# PI_Servo_Shield.net
KiCad netlist of a schematic drawn in EAGLE
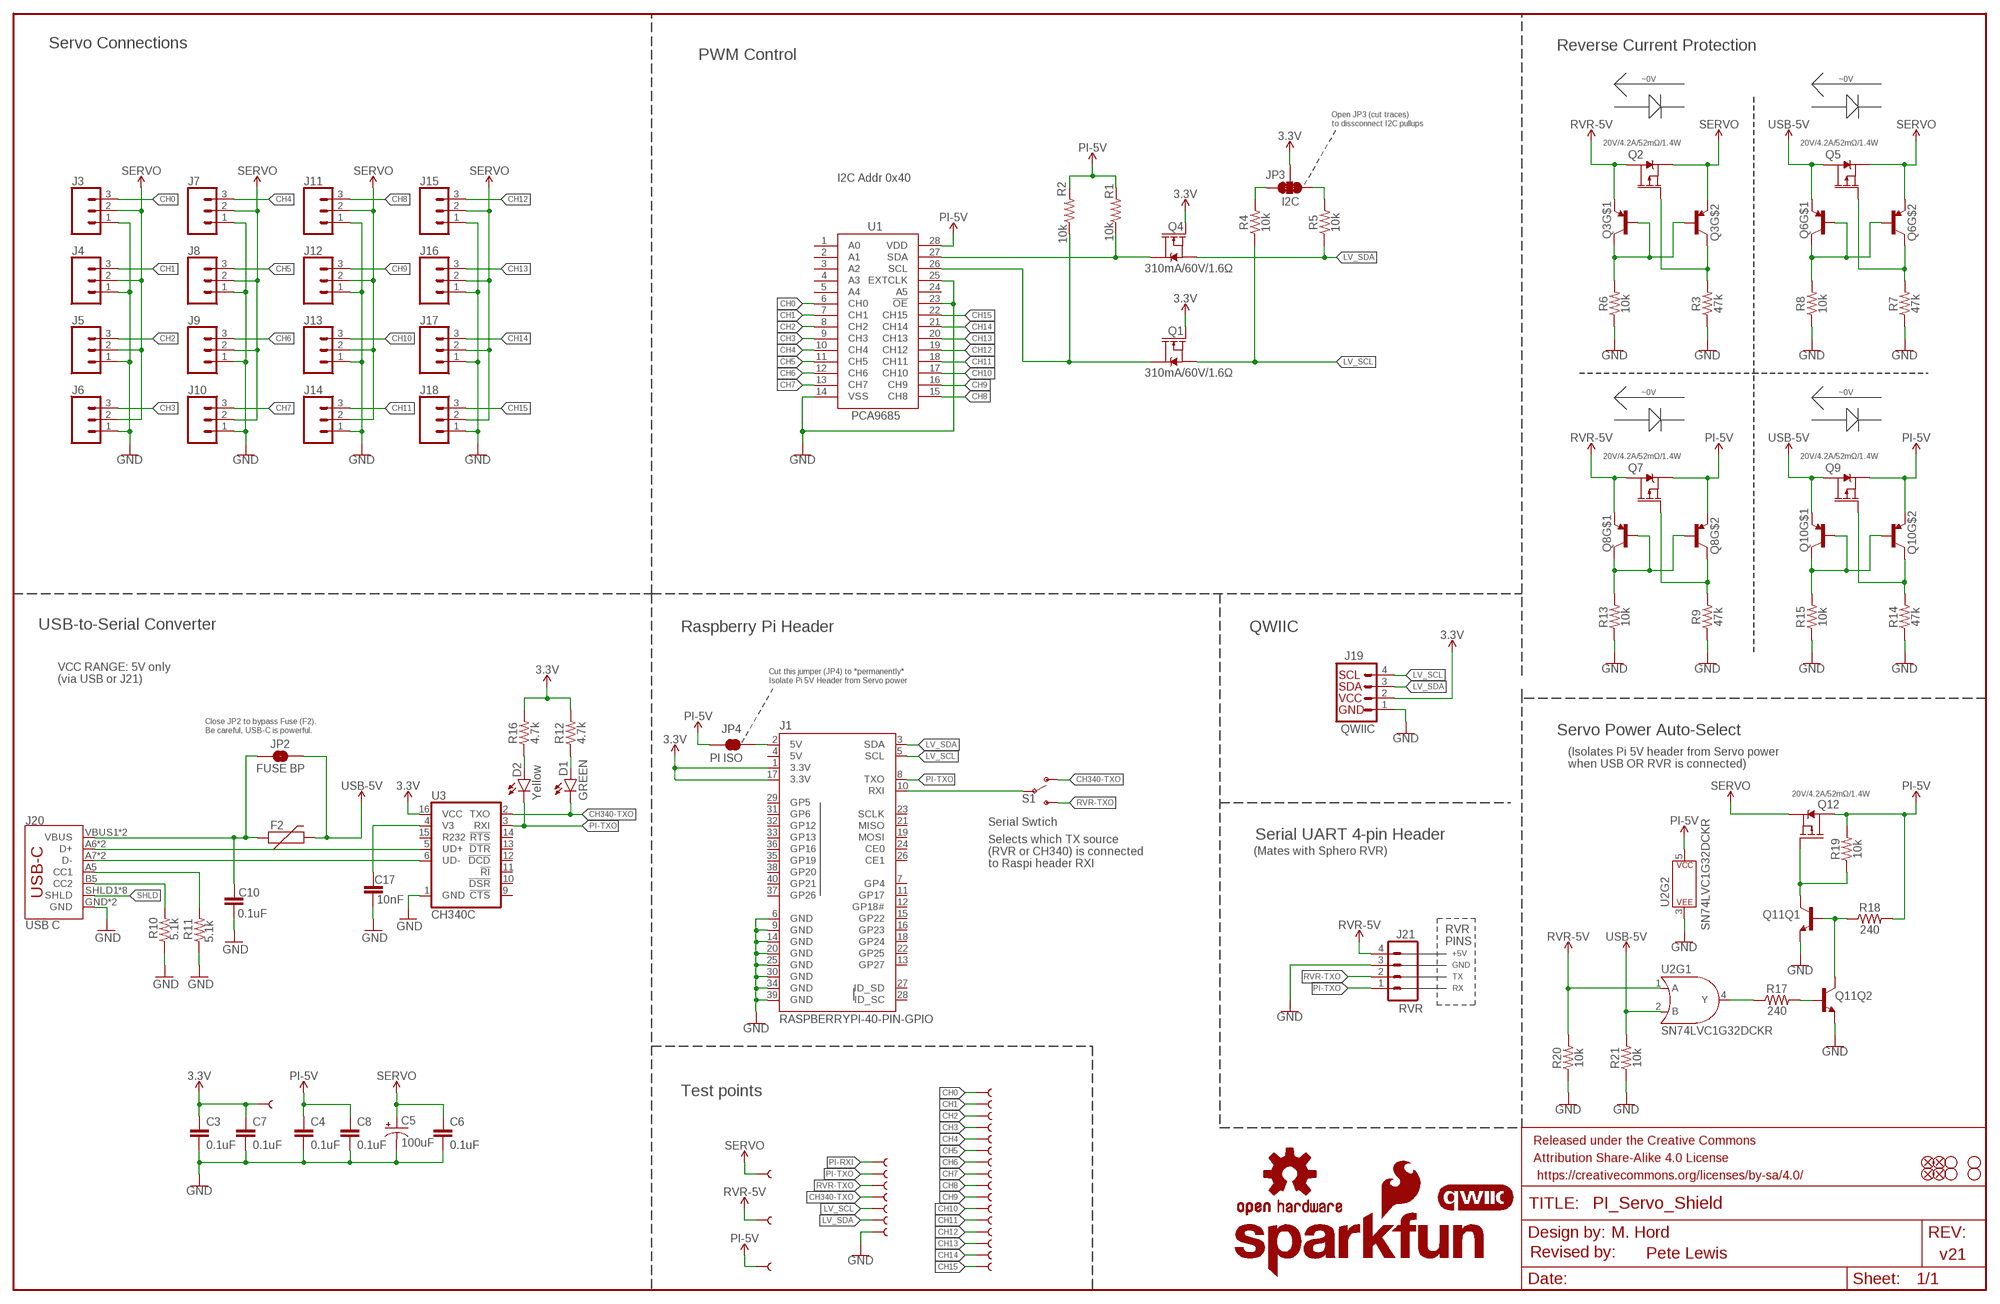
[diagram p0: schematic, sheet 1]

(export (version "E")
  (design (tool "Eeschema 10.0.6"))
  (components
    (comp (ref "C3")
      (value "0.1uF")
      (footprint "eagle-import:0603")
      (libsource (lib "eagle-import") (part "0.1UF-0603-25V-(+80/-20%)"))
    )
    (comp (ref "C4")
      (value "0.1uF")
      (footprint "eagle-import:0603")
      (libsource (lib "eagle-import") (part "0.1UF-0603-25V-(+80/-20%)"))
    )
    (comp (ref "C5")
      (value "100uF")
      (footprint "eagle-import:PANASONIC_D")
      (libsource (lib "eagle-import") (part "100UF-POLAR-25V-20%(ELEC)"))
    )
    (comp (ref "C6")
      (value "0.1uF")
      (footprint "eagle-import:0603")
      (libsource (lib "eagle-import") (part "0.1UF-0603-25V-(+80/-20%)"))
    )
    (comp (ref "C7")
      (value "0.1uF")
      (footprint "eagle-import:0603")
      (libsource (lib "eagle-import") (part "0.1UF-0603-25V-(+80/-20%)"))
    )
    (comp (ref "C8")
      (value "0.1uF")
      (footprint "eagle-import:0603")
      (libsource (lib "eagle-import") (part "0.1UF-0603-25V-(+80/-20%)"))
    )
    (comp (ref "C10")
      (value "0.1uF")
      (footprint "eagle-import:0603")
      (libsource (lib "eagle-import") (part "0.1UF-0603-25V-(+80/-20%)"))
    )
    (comp (ref "C17")
      (value "10nF")
      (footprint "eagle-import:0603")
      (libsource (lib "eagle-import") (part "10NF-0603-50V-10%"))
    )
    (comp (ref "D1")
      (value "GREEN")
      (footprint "eagle-import:LED-0603")
      (libsource (lib "eagle-import") (part "LED-GREEN0603"))
    )
    (comp (ref "D2")
      (value "Yellow")
      (footprint "eagle-import:LED-0603")
      (libsource (lib "eagle-import") (part "LED-YELLOW0603"))
    )
    (comp (ref "F2")
      (value "16V/2.5A(5A TRIP)")
      (footprint "eagle-import:1812")
      (libsource (lib "eagle-import") (part "PPTC_16V_2.5A"))
    )
    (comp (ref "FD1")
      (value "FIDUCIALUFIDUCIAL")
      (footprint "eagle-import:FIDUCIAL-MICRO")
      (libsource (lib "eagle-import") (part "FIDUCIALUFIDUCIAL"))
    )
    (comp (ref "FD2")
      (value "FIDUCIALUFIDUCIAL")
      (footprint "eagle-import:FIDUCIAL-MICRO")
      (libsource (lib "eagle-import") (part "FIDUCIALUFIDUCIAL"))
    )
    (comp (ref "FD3")
      (value "FIDUCIALUFIDUCIAL")
      (footprint "eagle-import:FIDUCIAL-MICRO")
      (libsource (lib "eagle-import") (part "FIDUCIALUFIDUCIAL"))
    )
    (comp (ref "FD4")
      (value "FIDUCIALUFIDUCIAL")
      (footprint "eagle-import:FIDUCIAL-MICRO")
      (libsource (lib "eagle-import") (part "FIDUCIALUFIDUCIAL"))
    )
    (comp (ref "FRAME2")
      (value "FRAME-LEDGER")
      (footprint "eagle-import:CREATIVE_COMMONS")
      (libsource (lib "eagle-import") (part "FRAME-LEDGER"))
    )
    (comp (ref "H1")
      (value "STAND-OFF")
      (footprint "eagle-import:STAND-OFF")
      (libsource (lib "eagle-import") (part "STAND-OFF"))
    )
    (comp (ref "H2")
      (value "STAND-OFF")
      (footprint "eagle-import:STAND-OFF")
      (libsource (lib "eagle-import") (part "STAND-OFF"))
    )
    (comp (ref "H3")
      (value "STAND-OFF")
      (footprint "eagle-import:STAND-OFF")
      (libsource (lib "eagle-import") (part "STAND-OFF"))
    )
    (comp (ref "H4")
      (value "STAND-OFF")
      (footprint "eagle-import:STAND-OFF")
      (libsource (lib "eagle-import") (part "STAND-OFF"))
    )
    (comp (ref "J1")
      (value "RASPBERRYPI-40-PIN-GPIO")
      (footprint "eagle-import:2X20")
      (libsource (lib "eagle-import") (part "RASPBERRYPI-40-PIN-GPIO_PTH_NO_SHROUD"))
    )
    (comp (ref "J3")
      (value "CONN_03")
      (footprint "eagle-import:1X03")
      (libsource (lib "eagle-import") (part "CONN_03"))
    )
    (comp (ref "J4")
      (value "CONN_03")
      (footprint "eagle-import:1X03")
      (libsource (lib "eagle-import") (part "CONN_03"))
    )
    (comp (ref "J5")
      (value "CONN_03")
      (footprint "eagle-import:1X03")
      (libsource (lib "eagle-import") (part "CONN_03"))
    )
    (comp (ref "J6")
      (value "CONN_03")
      (footprint "eagle-import:1X03")
      (libsource (lib "eagle-import") (part "CONN_03"))
    )
    (comp (ref "J7")
      (value "CONN_03")
      (footprint "eagle-import:1X03")
      (libsource (lib "eagle-import") (part "CONN_03"))
    )
    (comp (ref "J8")
      (value "CONN_03")
      (footprint "eagle-import:1X03")
      (libsource (lib "eagle-import") (part "CONN_03"))
    )
    (comp (ref "J9")
      (value "CONN_03")
      (footprint "eagle-import:1X03")
      (libsource (lib "eagle-import") (part "CONN_03"))
    )
    (comp (ref "J10")
      (value "CONN_03")
      (footprint "eagle-import:1X03")
      (libsource (lib "eagle-import") (part "CONN_03"))
    )
    (comp (ref "J11")
      (value "CONN_03")
      (footprint "eagle-import:1X03")
      (libsource (lib "eagle-import") (part "CONN_03"))
    )
    (comp (ref "J12")
      (value "CONN_03")
      (footprint "eagle-import:1X03")
      (libsource (lib "eagle-import") (part "CONN_03"))
    )
    (comp (ref "J13")
      (value "CONN_03")
      (footprint "eagle-import:1X03")
      (libsource (lib "eagle-import") (part "CONN_03"))
    )
    (comp (ref "J14")
      (value "CONN_03")
      (footprint "eagle-import:1X03")
      (libsource (lib "eagle-import") (part "CONN_03"))
    )
    (comp (ref "J15")
      (value "CONN_03")
      (footprint "eagle-import:1X03")
      (libsource (lib "eagle-import") (part "CONN_03"))
    )
    (comp (ref "J16")
      (value "CONN_03")
      (footprint "eagle-import:1X03")
      (libsource (lib "eagle-import") (part "CONN_03"))
    )
    (comp (ref "J17")
      (value "CONN_03")
      (footprint "eagle-import:1X03")
      (libsource (lib "eagle-import") (part "CONN_03"))
    )
    (comp (ref "J18")
      (value "CONN_03")
      (footprint "eagle-import:1X03")
      (libsource (lib "eagle-import") (part "CONN_03"))
    )
    (comp (ref "J19")
      (value "QWIIC")
      (footprint "eagle-import:JST04_1MM_RA")
      (libsource (lib "eagle-import") (part "QWIIC_CONNECTORJS-1MM"))
    )
    (comp (ref "J20")
      (value "USB C")
      (footprint "eagle-import:USB-C-16P")
      (libsource (lib "eagle-import") (part "USB_C16PIN"))
    )
    (comp (ref "J21")
      (value "RVR")
      (footprint "eagle-import:1X04_LOCK")
      (libsource (lib "eagle-import") (part "CONN_04LOCK"))
    )
    (comp (ref "JP2")
      (value "FUSE BP")
      (footprint "eagle-import:SMT-JUMPER_2_NO_SILK")
      (libsource (lib "eagle-import") (part "JUMPER-SMT_2_NO_SILK"))
    )
    (comp (ref "JP3")
      (value "I2C")
      (footprint "eagle-import:SMT-JUMPER_3_2-NC_TRACE_SILK")
      (libsource (lib "eagle-import") (part "JUMPER-SMT_3_2-NC_TRACE_SILK"))
    )
    (comp (ref "JP4")
      (value "PI ISO")
      (footprint "eagle-import:SMT-JUMPER_2_NC_TRACE_SILK")
      (libsource (lib "eagle-import") (part "JUMPER-SMT_2_NC_TRACE_SILK"))
    )
    (comp (ref "LOGO1")
      (value "SFE_LOGO_NAME_FLAME.1_INCH")
      (footprint "eagle-import:SFE_LOGO_NAME_FLAME_.1")
      (libsource (lib "eagle-import") (part "SFE_LOGO_NAME_FLAME.1_INCH"))
    )
    (comp (ref "LOGO2")
      (value "OSHW-LOGOS")
      (footprint "eagle-import:OSHW-LOGO-S")
      (libsource (lib "eagle-import") (part "OSHW-LOGOS"))
    )
    (comp (ref "Q1")
      (value "310mA/60V/1.6Ω")
      (footprint "eagle-import:SOT323")
      (libsource (lib "eagle-import") (part "MOSFET-NCH-2N7002PW"))
    )
    (comp (ref "Q2")
      (value "20V/4.2A/52mΩ/1.4W")
      (footprint "eagle-import:SOT23-3")
      (libsource (lib "eagle-import") (part "MOSFET_PCH-DMG2305UX-7"))
    )
    (comp (ref "Q3")
      (value "TRANS_PNP_DUALSOT-363")
      (footprint "eagle-import:SOT363_PHILIPS")
      (libsource (lib "eagle-import") (part "TRANS_PNP_DUALSOT-363"))
    )
    (comp (ref "Q4")
      (value "310mA/60V/1.6Ω")
      (footprint "eagle-import:SOT323")
      (libsource (lib "eagle-import") (part "MOSFET-NCH-2N7002PW"))
    )
    (comp (ref "Q5")
      (value "20V/4.2A/52mΩ/1.4W")
      (footprint "eagle-import:SOT23-3")
      (libsource (lib "eagle-import") (part "MOSFET_PCH-DMG2305UX-7"))
    )
    (comp (ref "Q6")
      (value "TRANS_PNP_DUALSOT-363")
      (footprint "eagle-import:SOT363_PHILIPS")
      (libsource (lib "eagle-import") (part "TRANS_PNP_DUALSOT-363"))
    )
    (comp (ref "Q7")
      (value "20V/4.2A/52mΩ/1.4W")
      (footprint "eagle-import:SOT23-3")
      (libsource (lib "eagle-import") (part "MOSFET_PCH-DMG2305UX-7"))
    )
    (comp (ref "Q8")
      (value "TRANS_PNP_DUALSOT-363")
      (footprint "eagle-import:SOT363_PHILIPS")
      (libsource (lib "eagle-import") (part "TRANS_PNP_DUALSOT-363"))
    )
    (comp (ref "Q9")
      (value "20V/4.2A/52mΩ/1.4W")
      (footprint "eagle-import:SOT23-3")
      (libsource (lib "eagle-import") (part "MOSFET_PCH-DMG2305UX-7"))
    )
    (comp (ref "Q10")
      (value "TRANS_PNP_DUALSOT-363")
      (footprint "eagle-import:SOT363_PHILIPS")
      (libsource (lib "eagle-import") (part "TRANS_PNP_DUALSOT-363"))
    )
    (comp (ref "Q11")
      (value "TRANS_NPN_DUAL-MBT3904DW1T1")
      (footprint "eagle-import:SC70-6")
      (libsource (lib "eagle-import") (part "TRANS_NPN_DUAL-MBT3904DW1T1"))
    )
    (comp (ref "Q12")
      (value "20V/4.2A/52mΩ/1.4W")
      (footprint "eagle-import:SOT23-3")
      (libsource (lib "eagle-import") (part "MOSFET_PCH-DMG2305UX-7"))
    )
    (comp (ref "R1")
      (value "10k")
      (footprint "eagle-import:0603")
      (libsource (lib "eagle-import") (part "10KOHM-0603-1/10W-1%"))
    )
    (comp (ref "R2")
      (value "10k")
      (footprint "eagle-import:0603")
      (libsource (lib "eagle-import") (part "10KOHM-0603-1/10W-1%"))
    )
    (comp (ref "R3")
      (value "47k")
      (footprint "eagle-import:0603")
      (libsource (lib "eagle-import") (part "47KOHM-0603-1/10W-1%"))
    )
    (comp (ref "R4")
      (value "10k")
      (footprint "eagle-import:0603")
      (libsource (lib "eagle-import") (part "10KOHM-0603-1/10W-1%"))
    )
    (comp (ref "R5")
      (value "10k")
      (footprint "eagle-import:0603")
      (libsource (lib "eagle-import") (part "10KOHM-0603-1/10W-1%"))
    )
    (comp (ref "R6")
      (value "10k")
      (footprint "eagle-import:0603")
      (libsource (lib "eagle-import") (part "10KOHM-0603-1/10W-1%"))
    )
    (comp (ref "R7")
      (value "47k")
      (footprint "eagle-import:0603")
      (libsource (lib "eagle-import") (part "47KOHM-0603-1/10W-1%"))
    )
    (comp (ref "R8")
      (value "10k")
      (footprint "eagle-import:0603")
      (libsource (lib "eagle-import") (part "10KOHM-0603-1/10W-1%"))
    )
    (comp (ref "R9")
      (value "47k")
      (footprint "eagle-import:0603")
      (libsource (lib "eagle-import") (part "47KOHM-0603-1/10W-1%"))
    )
    (comp (ref "R10")
      (value "5.1k")
      (footprint "eagle-import:0603")
      (libsource (lib "eagle-import") (part "5.1KOHM5.1KOHM-0603-1/10W-1%"))
    )
    (comp (ref "R11")
      (value "5.1k")
      (footprint "eagle-import:0603")
      (libsource (lib "eagle-import") (part "5.1KOHM5.1KOHM-0603-1/10W-1%"))
    )
    (comp (ref "R12")
      (value "4.7k")
      (footprint "eagle-import:0603")
      (libsource (lib "eagle-import") (part "4.7KOHM-0603-1/10W-1%"))
    )
    (comp (ref "R13")
      (value "10k")
      (footprint "eagle-import:0603")
      (libsource (lib "eagle-import") (part "10KOHM-0603-1/10W-1%"))
    )
    (comp (ref "R14")
      (value "47k")
      (footprint "eagle-import:0603")
      (libsource (lib "eagle-import") (part "47KOHM-0603-1/10W-1%"))
    )
    (comp (ref "R15")
      (value "10k")
      (footprint "eagle-import:0603")
      (libsource (lib "eagle-import") (part "10KOHM-0603-1/10W-1%"))
    )
    (comp (ref "R16")
      (value "4.7k")
      (footprint "eagle-import:0603")
      (libsource (lib "eagle-import") (part "4.7KOHM-0603-1/10W-1%"))
    )
    (comp (ref "R17")
      (value "240")
      (footprint "eagle-import:0603")
      (libsource (lib "eagle-import") (part "240OHM-0603-1/10W-1%"))
    )
    (comp (ref "R18")
      (value "240")
      (footprint "eagle-import:0603")
      (libsource (lib "eagle-import") (part "240OHM-0603-1/10W-1%"))
    )
    (comp (ref "R19")
      (value "10k")
      (footprint "eagle-import:0603")
      (libsource (lib "eagle-import") (part "10KOHM-0603-1/10W-1%"))
    )
    (comp (ref "R20")
      (value "10k")
      (footprint "eagle-import:0603")
      (libsource (lib "eagle-import") (part "10KOHM-0603-1/10W-1%"))
    )
    (comp (ref "R21")
      (value "10k")
      (footprint "eagle-import:0603")
      (libsource (lib "eagle-import") (part "10KOHM-0603-1/10W-1%"))
    )
    (comp (ref "S1")
      (value "SWITCH-SPDT-SMD-RIGHT-ANGLE")
      (footprint "eagle-import:SWITCH_SPST_SMD_A")
      (libsource (lib "eagle-import") (part "SWITCH-SPDT-SMD-RIGHT-ANGLE"))
    )
    (comp (ref "TP0")
      (value "TEST-POINT3X4")
      (footprint "eagle-import:PAD.03X.04")
      (libsource (lib "eagle-import") (part "TEST-POINT3X4"))
    )
    (comp (ref "TP1")
      (value "TEST-POINT3X4")
      (footprint "eagle-import:PAD.03X.04")
      (libsource (lib "eagle-import") (part "TEST-POINT3X4"))
    )
    (comp (ref "TP2")
      (value "TEST-POINT3X4")
      (footprint "eagle-import:PAD.03X.04")
      (libsource (lib "eagle-import") (part "TEST-POINT3X4"))
    )
    (comp (ref "TP3")
      (value "TEST-POINT3X4")
      (footprint "eagle-import:PAD.03X.04")
      (libsource (lib "eagle-import") (part "TEST-POINT3X4"))
    )
    (comp (ref "TP4")
      (value "TEST-POINT3X4")
      (footprint "eagle-import:PAD.03X.04")
      (libsource (lib "eagle-import") (part "TEST-POINT3X4"))
    )
    (comp (ref "TP5")
      (value "TEST-POINT3X4")
      (footprint "eagle-import:PAD.03X.04")
      (libsource (lib "eagle-import") (part "TEST-POINT3X4"))
    )
    (comp (ref "TP6")
      (value "TEST-POINT3X4")
      (footprint "eagle-import:PAD.03X.04")
      (libsource (lib "eagle-import") (part "TEST-POINT3X4"))
    )
    (comp (ref "TP7")
      (value "TEST-POINT3X4")
      (footprint "eagle-import:PAD.03X.04")
      (libsource (lib "eagle-import") (part "TEST-POINT3X4"))
    )
    (comp (ref "TP8")
      (value "TEST-POINT3X4")
      (footprint "eagle-import:PAD.03X.04")
      (libsource (lib "eagle-import") (part "TEST-POINT3X4"))
    )
    (comp (ref "TP9")
      (value "TEST-POINT3X4")
      (footprint "eagle-import:PAD.03X.04")
      (libsource (lib "eagle-import") (part "TEST-POINT3X4"))
    )
    (comp (ref "TP10")
      (value "TEST-POINT3X4")
      (footprint "eagle-import:PAD.03X.04")
      (libsource (lib "eagle-import") (part "TEST-POINT3X4"))
    )
    (comp (ref "TP11")
      (value "TEST-POINT3X4")
      (footprint "eagle-import:PAD.03X.04")
      (libsource (lib "eagle-import") (part "TEST-POINT3X4"))
    )
    (comp (ref "TP12")
      (value "TEST-POINT3X4")
      (footprint "eagle-import:PAD.03X.04")
      (libsource (lib "eagle-import") (part "TEST-POINT3X4"))
    )
    (comp (ref "TP13")
      (value "TEST-POINT3X4")
      (footprint "eagle-import:PAD.03X.04")
      (libsource (lib "eagle-import") (part "TEST-POINT3X4"))
    )
    (comp (ref "TP14")
      (value "TEST-POINT3X4")
      (footprint "eagle-import:PAD.03X.04")
      (libsource (lib "eagle-import") (part "TEST-POINT3X4"))
    )
    (comp (ref "TP15")
      (value "TEST-POINT3X4")
      (footprint "eagle-import:PAD.03X.04")
      (libsource (lib "eagle-import") (part "TEST-POINT3X4"))
    )
    (comp (ref "TP16")
      (value "TEST-POINT3X4")
      (footprint "eagle-import:PAD.03X.04")
      (libsource (lib "eagle-import") (part "TEST-POINT3X4"))
    )
    (comp (ref "TP17")
      (value "TEST-POINT3X4")
      (footprint "eagle-import:PAD.03X.04")
      (libsource (lib "eagle-import") (part "TEST-POINT3X4"))
    )
    (comp (ref "TP18")
      (value "TEST-POINTTP_15TH_THRU")
      (footprint "eagle-import:TP_15TH")
      (libsource (lib "eagle-import") (part "TEST-POINTTP_15TH_THRU"))
    )
    (comp (ref "TP19")
      (value "TEST-POINTTP_15TH_THRU")
      (footprint "eagle-import:TP_15TH")
      (libsource (lib "eagle-import") (part "TEST-POINTTP_15TH_THRU"))
    )
    (comp (ref "TP20")
      (value "TEST-POINT3X4")
      (footprint "eagle-import:PAD.03X.04")
      (libsource (lib "eagle-import") (part "TEST-POINT3X4"))
    )
    (comp (ref "TP21")
      (value "TEST-POINT3X4")
      (footprint "eagle-import:PAD.03X.04")
      (libsource (lib "eagle-import") (part "TEST-POINT3X4"))
    )
    (comp (ref "TP22")
      (value "TEST-POINT3X4")
      (footprint "eagle-import:PAD.03X.04")
      (libsource (lib "eagle-import") (part "TEST-POINT3X4"))
    )
    (comp (ref "TP23")
      (value "TEST-POINT3X4")
      (footprint "eagle-import:PAD.03X.04")
      (libsource (lib "eagle-import") (part "TEST-POINT3X4"))
    )
    (comp (ref "TP24")
      (value "TEST-POINT3X4")
      (footprint "eagle-import:PAD.03X.04")
      (libsource (lib "eagle-import") (part "TEST-POINT3X4"))
    )
    (comp (ref "TP25")
      (value "TEST-POINT3X4")
      (footprint "eagle-import:PAD.03X.04")
      (libsource (lib "eagle-import") (part "TEST-POINT3X4"))
    )
    (comp (ref "TP26")
      (value "TEST-POINT3X4")
      (footprint "eagle-import:PAD.03X.04")
      (libsource (lib "eagle-import") (part "TEST-POINT3X4"))
    )
    (comp (ref "U$1")
      (value "QWIIC_LOGO_5MM")
      (footprint "eagle-import:QWIIC_5MM")
      (libsource (lib "eagle-import") (part "QWIIC_LOGO_5MM"))
    )
    (comp (ref "U1")
      (value "PCA9685")
      (footprint "eagle-import:TSSOP-28_4MM")
      (libsource (lib "eagle-import") (part "PCA9685"))
    )
    (comp (ref "U2")
      (value "SN74LVC1G32DCKR")
      (footprint "eagle-import:SOT353")
      (libsource (lib "eagle-import") (part "7432"))
    )
    (comp (ref "U3")
      (value "CH340C")
      (footprint "eagle-import:SO016")
      (libsource (lib "eagle-import") (part "CH340C"))
    )
  )
  (nets
    (net (code "1") (name "/5V") (class "Default")
      (node (ref "J1") (pin "4") (pinfunction "5V_4") (pintype "power_in"))
    )
    (net (code "2") (name "3.3V") (class "Default")
      (node (ref "C3") (pin "1") (pinfunction "1_1") (pintype "passive"))
      (node (ref "C7") (pin "1") (pinfunction "1_1") (pintype "passive"))
      (node (ref "J1") (pin "1") (pinfunction "3.3V_1") (pintype "power_in"))
      (node (ref "J1") (pin "17") (pinfunction "3.3V_17") (pintype "power_in"))
      (node (ref "J19") (pin "2") (pinfunction "2_2") (pintype "power_in"))
      (node (ref "JP3") (pin "2") (pinfunction "2_2") (pintype "passive"))
      (node (ref "Q1") (pin "1") (pinfunction "G_1") (pintype "bidirectional"))
      (node (ref "Q4") (pin "1") (pinfunction "G_1") (pintype "bidirectional"))
      (node (ref "R12") (pin "2") (pinfunction "2_2") (pintype "passive"))
      (node (ref "R16") (pin "2") (pinfunction "2_2") (pintype "passive"))
      (node (ref "TP22") (pin "P$1") (pinfunction "1_P$1") (pintype "bidirectional"))
      (node (ref "U3") (pin "16") (pinfunction "VCC_16") (pintype "bidirectional"))
    )
    (net (code "3") (name "CH0") (class "Default")
      (node (ref "J3") (pin "3") (pinfunction "3_3") (pintype "passive"))
      (node (ref "TP0") (pin "P$1") (pinfunction "1_P$1") (pintype "bidirectional"))
      (node (ref "U1") (pin "6") (pinfunction "CH0_6") (pintype "bidirectional"))
    )
    (net (code "4") (name "CH1") (class "Default")
      (node (ref "J4") (pin "3") (pinfunction "3_3") (pintype "passive"))
      (node (ref "TP1") (pin "P$1") (pinfunction "1_P$1") (pintype "bidirectional"))
      (node (ref "U1") (pin "7") (pinfunction "CH1_7") (pintype "bidirectional"))
    )
    (net (code "5") (name "CH2") (class "Default")
      (node (ref "J5") (pin "3") (pinfunction "3_3") (pintype "passive"))
      (node (ref "TP2") (pin "P$1") (pinfunction "1_P$1") (pintype "bidirectional"))
      (node (ref "U1") (pin "8") (pinfunction "CH2_8") (pintype "bidirectional"))
    )
    (net (code "6") (name "CH3") (class "Default")
      (node (ref "J6") (pin "3") (pinfunction "3_3") (pintype "passive"))
      (node (ref "TP3") (pin "P$1") (pinfunction "1_P$1") (pintype "bidirectional"))
      (node (ref "U1") (pin "9") (pinfunction "CH3_9") (pintype "bidirectional"))
    )
    (net (code "7") (name "CH4") (class "Default")
      (node (ref "J7") (pin "3") (pinfunction "3_3") (pintype "passive"))
      (node (ref "TP4") (pin "P$1") (pinfunction "1_P$1") (pintype "bidirectional"))
      (node (ref "U1") (pin "10") (pinfunction "CH4_10") (pintype "bidirectional"))
    )
    (net (code "8") (name "CH5") (class "Default")
      (node (ref "J8") (pin "3") (pinfunction "3_3") (pintype "passive"))
      (node (ref "TP5") (pin "P$1") (pinfunction "1_P$1") (pintype "bidirectional"))
      (node (ref "U1") (pin "11") (pinfunction "CH5_11") (pintype "bidirectional"))
    )
    (net (code "9") (name "CH6") (class "Default")
      (node (ref "J9") (pin "3") (pinfunction "3_3") (pintype "passive"))
      (node (ref "TP6") (pin "P$1") (pinfunction "1_P$1") (pintype "bidirectional"))
      (node (ref "U1") (pin "12") (pinfunction "CH6_12") (pintype "bidirectional"))
    )
    (net (code "10") (name "CH7") (class "Default")
      (node (ref "J10") (pin "3") (pinfunction "3_3") (pintype "passive"))
      (node (ref "TP7") (pin "P$1") (pinfunction "1_P$1") (pintype "bidirectional"))
      (node (ref "U1") (pin "13") (pinfunction "CH7_13") (pintype "bidirectional"))
    )
    (net (code "11") (name "CH8") (class "Default")
      (node (ref "J11") (pin "3") (pinfunction "3_3") (pintype "passive"))
      (node (ref "TP8") (pin "P$1") (pinfunction "1_P$1") (pintype "bidirectional"))
      (node (ref "U1") (pin "15") (pinfunction "CH8_15") (pintype "bidirectional"))
    )
    (net (code "12") (name "CH9") (class "Default")
      (node (ref "J12") (pin "3") (pinfunction "3_3") (pintype "passive"))
      (node (ref "TP9") (pin "P$1") (pinfunction "1_P$1") (pintype "bidirectional"))
      (node (ref "U1") (pin "16") (pinfunction "CH9_16") (pintype "bidirectional"))
    )
    (net (code "13") (name "CH10") (class "Default")
      (node (ref "J13") (pin "3") (pinfunction "3_3") (pintype "passive"))
      (node (ref "TP10") (pin "P$1") (pinfunction "1_P$1") (pintype "bidirectional"))
      (node (ref "U1") (pin "17") (pinfunction "CH10_17") (pintype "bidirectional"))
    )
    (net (code "14") (name "CH11") (class "Default")
      (node (ref "J14") (pin "3") (pinfunction "3_3") (pintype "passive"))
      (node (ref "TP11") (pin "P$1") (pinfunction "1_P$1") (pintype "bidirectional"))
      (node (ref "U1") (pin "18") (pinfunction "CH11_18") (pintype "bidirectional"))
    )
    (net (code "15") (name "CH12") (class "Default")
      (node (ref "J15") (pin "3") (pinfunction "3_3") (pintype "passive"))
      (node (ref "TP12") (pin "P$1") (pinfunction "1_P$1") (pintype "bidirectional"))
      (node (ref "U1") (pin "19") (pinfunction "CH12_19") (pintype "bidirectional"))
    )
    (net (code "16") (name "CH13") (class "Default")
      (node (ref "J16") (pin "3") (pinfunction "3_3") (pintype "passive"))
      (node (ref "TP13") (pin "P$1") (pinfunction "1_P$1") (pintype "bidirectional"))
      (node (ref "U1") (pin "20") (pinfunction "CH13_20") (pintype "bidirectional"))
    )
    (net (code "17") (name "CH14") (class "Default")
      (node (ref "J17") (pin "3") (pinfunction "3_3") (pintype "passive"))
      (node (ref "TP14") (pin "P$1") (pinfunction "1_P$1") (pintype "bidirectional"))
      (node (ref "U1") (pin "21") (pinfunction "CH14_21") (pintype "bidirectional"))
    )
    (net (code "18") (name "CH15") (class "Default")
      (node (ref "J18") (pin "3") (pinfunction "3_3") (pintype "passive"))
      (node (ref "TP15") (pin "P$1") (pinfunction "1_P$1") (pintype "bidirectional"))
      (node (ref "U1") (pin "22") (pinfunction "CH15_22") (pintype "bidirectional"))
    )
    (net (code "19") (name "CH340-TXO") (class "Default")
      (node (ref "D1") (pin "C") (pinfunction "C_C") (pintype "passive"))
      (node (ref "S1") (pin "1") (pinfunction "O_1") (pintype "passive"))
      (node (ref "TP23") (pin "P$1") (pinfunction "1_P$1") (pintype "bidirectional"))
      (node (ref "U3") (pin "2") (pinfunction "TXO_2") (pintype "bidirectional"))
    )
    (net (code "20") (name "GND") (class "Default")
      (node (ref "C10") (pin "2") (pinfunction "2_2") (pintype "passive"))
      (node (ref "C17") (pin "2") (pinfunction "2_2") (pintype "passive"))
      (node (ref "C3") (pin "2") (pinfunction "2_2") (pintype "passive"))
      (node (ref "C4") (pin "2") (pinfunction "2_2") (pintype "passive"))
      (node (ref "C5") (pin "-") (pinfunction "-_-") (pintype "passive"))
      (node (ref "C6") (pin "2") (pinfunction "2_2") (pintype "passive"))
      (node (ref "C7") (pin "2") (pinfunction "2_2") (pintype "passive"))
      (node (ref "C8") (pin "2") (pinfunction "2_2") (pintype "passive"))
      (node (ref "J1") (pin "14") (pinfunction "GND_14") (pintype "power_in"))
      (node (ref "J1") (pin "20") (pinfunction "GND_20") (pintype "power_in"))
      (node (ref "J1") (pin "25") (pinfunction "GND_25") (pintype "power_in"))
      (node (ref "J1") (pin "30") (pinfunction "GND_30") (pintype "power_in"))
      (node (ref "J1") (pin "34") (pinfunction "GND_34") (pintype "power_in"))
      (node (ref "J1") (pin "39") (pinfunction "GND_39") (pintype "power_in"))
      (node (ref "J1") (pin "6") (pinfunction "GND_6") (pintype "power_in"))
      (node (ref "J1") (pin "9") (pinfunction "GND_9") (pintype "power_in"))
      (node (ref "J10") (pin "1") (pinfunction "1_1") (pintype "passive"))
      (node (ref "J11") (pin "1") (pinfunction "1_1") (pintype "passive"))
      (node (ref "J12") (pin "1") (pinfunction "1_1") (pintype "passive"))
      (node (ref "J13") (pin "1") (pinfunction "1_1") (pintype "passive"))
      (node (ref "J14") (pin "1") (pinfunction "1_1") (pintype "passive"))
      (node (ref "J15") (pin "1") (pinfunction "1_1") (pintype "passive"))
      (node (ref "J16") (pin "1") (pinfunction "1_1") (pintype "passive"))
      (node (ref "J17") (pin "1") (pinfunction "1_1") (pintype "passive"))
      (node (ref "J18") (pin "1") (pinfunction "1_1") (pintype "passive"))
      (node (ref "J19") (pin "1") (pinfunction "1_1") (pintype "power_in"))
      (node (ref "J20") (pin "GND") (pinfunction "GND_GND") (pintype "bidirectional"))
      (node (ref "J20") (pin "GND2") (pinfunction "GND_GND2") (pintype "bidirectional"))
      (node (ref "J21") (pin "3") (pinfunction "3_3") (pintype "passive"))
      (node (ref "J3") (pin "1") (pinfunction "1_1") (pintype "passive"))
      (node (ref "J4") (pin "1") (pinfunction "1_1") (pintype "passive"))
      (node (ref "J5") (pin "1") (pinfunction "1_1") (pintype "passive"))
      (node (ref "J6") (pin "1") (pinfunction "1_1") (pintype "passive"))
      (node (ref "J7") (pin "1") (pinfunction "1_1") (pintype "passive"))
      (node (ref "J8") (pin "1") (pinfunction "1_1") (pintype "passive"))
      (node (ref "J9") (pin "1") (pinfunction "1_1") (pintype "passive"))
      (node (ref "Q11") (pin "1") (pinfunction "E_1") (pintype "passive"))
      (node (ref "Q11") (pin "4") (pinfunction "E_4") (pintype "passive"))
      (node (ref "R10") (pin "1") (pinfunction "1_1") (pintype "passive"))
      (node (ref "R11") (pin "1") (pinfunction "1_1") (pintype "passive"))
      (node (ref "R13") (pin "1") (pinfunction "1_1") (pintype "passive"))
      (node (ref "R14") (pin "1") (pinfunction "1_1") (pintype "passive"))
      (node (ref "R15") (pin "1") (pinfunction "1_1") (pintype "passive"))
      (node (ref "R20") (pin "1") (pinfunction "1_1") (pintype "passive"))
      (node (ref "R21") (pin "1") (pinfunction "1_1") (pintype "passive"))
      (node (ref "R3") (pin "1") (pinfunction "1_1") (pintype "passive"))
      (node (ref "R6") (pin "1") (pinfunction "1_1") (pintype "passive"))
      (node (ref "R7") (pin "1") (pinfunction "1_1") (pintype "passive"))
      (node (ref "R8") (pin "1") (pinfunction "1_1") (pintype "passive"))
      (node (ref "R9") (pin "1") (pinfunction "1_1") (pintype "passive"))
      (node (ref "TP17") (pin "P$1") (pinfunction "1_P$1") (pintype "bidirectional"))
      (node (ref "U1") (pin "14") (pinfunction "VSS_14") (pintype "bidirectional"))
      (node (ref "U1") (pin "23") (pinfunction "~{OE}_23") (pintype "bidirectional"))
      (node (ref "U1") (pin "25") (pinfunction "EXTCLK_25") (pintype "bidirectional"))
      (node (ref "U2") (pin "3") (pinfunction "P$V-_3") (pintype "bidirectional"))
      (node (ref "U3") (pin "1") (pinfunction "GND_1") (pintype "bidirectional"))
    )
    (net (code "21") (name "LV_SCL") (class "Default")
      (node (ref "J1") (pin "5") (pinfunction "SCL_5") (pintype "bidirectional"))
      (node (ref "J19") (pin "4") (pinfunction "4_4") (pintype "passive"))
      (node (ref "Q1") (pin "2") (pinfunction "S_2") (pintype "bidirectional"))
      (node (ref "R4") (pin "1") (pinfunction "1_1") (pintype "passive"))
      (node (ref "TP18") (pin "P$1") (pinfunction "1_P$1") (pintype "bidirectional"))
    )
    (net (code "22") (name "LV_SDA") (class "Default")
      (node (ref "J1") (pin "3") (pinfunction "SDA_3") (pintype "bidirectional"))
      (node (ref "J19") (pin "3") (pinfunction "3_3") (pintype "passive"))
      (node (ref "Q4") (pin "2") (pinfunction "S_2") (pintype "bidirectional"))
      (node (ref "R5") (pin "1") (pinfunction "1_1") (pintype "passive"))
      (node (ref "TP19") (pin "P$1") (pinfunction "1_P$1") (pintype "bidirectional"))
    )
    (net (code "23") (name "Net-(C10-Pad1)") (class "Default")
      (node (ref "C10") (pin "1") (pinfunction "1_1") (pintype "passive"))
      (node (ref "F2") (pin "1") (pinfunction "1_1") (pintype "bidirectional"))
      (node (ref "J20") (pin "VBUS1") (pinfunction "VBUS_VBUS1") (pintype "bidirectional"))
      (node (ref "J20") (pin "VBUS2") (pinfunction "VBUS_VBUS2") (pintype "bidirectional"))
      (node (ref "JP2") (pin "1") (pinfunction "1_1") (pintype "passive"))
    )
    (net (code "24") (name "Net-(D1-PadA)") (class "Default")
      (node (ref "D1") (pin "A") (pinfunction "A_A") (pintype "passive"))
      (node (ref "R12") (pin "1") (pinfunction "1_1") (pintype "passive"))
    )
    (net (code "25") (name "Net-(D2-PadA)") (class "Default")
      (node (ref "D2") (pin "A") (pinfunction "A_A") (pintype "passive"))
      (node (ref "R16") (pin "1") (pinfunction "1_1") (pintype "passive"))
    )
    (net (code "26") (name "Net-(J1-5V-Pad2)") (class "Default")
      (node (ref "J1") (pin "2") (pinfunction "5V_2") (pintype "power_in"))
      (node (ref "JP4") (pin "2") (pinfunction "2_2") (pintype "passive"))
    )
    (net (code "27") (name "Net-(J20-CC1)") (class "Default")
      (node (ref "J20") (pin "A5") (pinfunction "CC1_A5") (pintype "bidirectional"))
      (node (ref "R11") (pin "2") (pinfunction "2_2") (pintype "passive"))
    )
    (net (code "28") (name "Net-(J20-CC2)") (class "Default")
      (node (ref "J20") (pin "B5") (pinfunction "CC2_B5") (pintype "bidirectional"))
      (node (ref "R10") (pin "2") (pinfunction "2_2") (pintype "passive"))
    )
    (net (code "29") (name "Net-(JP3-Pad1)") (class "Default")
      (node (ref "JP3") (pin "1") (pinfunction "1_1") (pintype "passive"))
      (node (ref "R5") (pin "2") (pinfunction "2_2") (pintype "passive"))
    )
    (net (code "30") (name "Net-(JP3-Pad3)") (class "Default")
      (node (ref "JP3") (pin "3") (pinfunction "3_3") (pintype "passive"))
      (node (ref "R4") (pin "2") (pinfunction "2_2") (pintype "passive"))
    )
    (net (code "31") (name "Net-(Q1-D)") (class "Default")
      (node (ref "Q1") (pin "3") (pinfunction "D_3") (pintype "bidirectional"))
      (node (ref "R2") (pin "1") (pinfunction "1_1") (pintype "passive"))
      (node (ref "U1") (pin "26") (pinfunction "SCL_26") (pintype "bidirectional"))
    )
    (net (code "32") (name "Net-(Q2-G)") (class "Default")
      (node (ref "Q2") (pin "1") (pinfunction "G_1") (pintype "bidirectional"))
      (node (ref "Q3") (pin "3") (pinfunction "C_3") (pintype "passive"))
      (node (ref "R3") (pin "2") (pinfunction "2_2") (pintype "passive"))
    )
    (net (code "33") (name "Net-(Q3A-B)") (class "Default")
      (node (ref "Q3") (pin "2") (pinfunction "B_2") (pintype "passive"))
      (node (ref "Q3") (pin "5") (pinfunction "B_5") (pintype "passive"))
      (node (ref "Q3") (pin "6") (pinfunction "C_6") (pintype "passive"))
      (node (ref "R6") (pin "2") (pinfunction "2_2") (pintype "passive"))
    )
    (net (code "34") (name "Net-(Q4-D)") (class "Default")
      (node (ref "Q4") (pin "3") (pinfunction "D_3") (pintype "bidirectional"))
      (node (ref "R1") (pin "1") (pinfunction "1_1") (pintype "passive"))
      (node (ref "U1") (pin "27") (pinfunction "SDA_27") (pintype "bidirectional"))
    )
    (net (code "35") (name "Net-(Q5-G)") (class "Default")
      (node (ref "Q5") (pin "1") (pinfunction "G_1") (pintype "bidirectional"))
      (node (ref "Q6") (pin "3") (pinfunction "C_3") (pintype "passive"))
      (node (ref "R7") (pin "2") (pinfunction "2_2") (pintype "passive"))
    )
    (net (code "36") (name "Net-(Q6A-B)") (class "Default")
      (node (ref "Q6") (pin "2") (pinfunction "B_2") (pintype "passive"))
      (node (ref "Q6") (pin "5") (pinfunction "B_5") (pintype "passive"))
      (node (ref "Q6") (pin "6") (pinfunction "C_6") (pintype "passive"))
      (node (ref "R8") (pin "2") (pinfunction "2_2") (pintype "passive"))
    )
    (net (code "37") (name "Net-(Q7-G)") (class "Default")
      (node (ref "Q7") (pin "1") (pinfunction "G_1") (pintype "bidirectional"))
      (node (ref "Q8") (pin "3") (pinfunction "C_3") (pintype "passive"))
      (node (ref "R9") (pin "2") (pinfunction "2_2") (pintype "passive"))
    )
    (net (code "38") (name "Net-(Q8A-B)") (class "Default")
      (node (ref "Q8") (pin "2") (pinfunction "B_2") (pintype "passive"))
      (node (ref "Q8") (pin "5") (pinfunction "B_5") (pintype "passive"))
      (node (ref "Q8") (pin "6") (pinfunction "C_6") (pintype "passive"))
      (node (ref "R13") (pin "2") (pinfunction "2_2") (pintype "passive"))
    )
    (net (code "39") (name "Net-(Q10A-B)") (class "Default")
      (node (ref "Q10") (pin "2") (pinfunction "B_2") (pintype "passive"))
      (node (ref "Q10") (pin "5") (pinfunction "B_5") (pintype "passive"))
      (node (ref "Q10") (pin "6") (pinfunction "C_6") (pintype "passive"))
      (node (ref "R15") (pin "2") (pinfunction "2_2") (pintype "passive"))
    )
    (net (code "40") (name "Net-(Q10B-C)") (class "Default")
      (node (ref "Q10") (pin "3") (pinfunction "C_3") (pintype "passive"))
      (node (ref "Q9") (pin "1") (pinfunction "G_1") (pintype "bidirectional"))
      (node (ref "R14") (pin "2") (pinfunction "2_2") (pintype "passive"))
    )
    (net (code "41") (name "Net-(Q11A-B)") (class "Default")
      (node (ref "Q11") (pin "5") (pinfunction "B_5") (pintype "passive"))
      (node (ref "Q11") (pin "6") (pinfunction "C_6") (pintype "passive"))
      (node (ref "R18") (pin "1") (pinfunction "1_1") (pintype "passive"))
    )
    (net (code "42") (name "Net-(Q11A-C)") (class "Default")
      (node (ref "Q11") (pin "3") (pinfunction "C_3") (pintype "passive"))
      (node (ref "Q12") (pin "1") (pinfunction "G_1") (pintype "bidirectional"))
      (node (ref "R19") (pin "1") (pinfunction "1_1") (pintype "passive"))
    )
    (net (code "43") (name "Net-(Q11B-B)") (class "Default")
      (node (ref "Q11") (pin "2") (pinfunction "B_2") (pintype "passive"))
      (node (ref "R17") (pin "2") (pinfunction "2_2") (pintype "passive"))
    )
    (net (code "44") (name "Net-(U2A-Y)") (class "Default")
      (node (ref "R17") (pin "1") (pinfunction "1_1") (pintype "passive"))
      (node (ref "U2") (pin "4") (pinfunction "Y_4") (pintype "bidirectional"))
    )
    (net (code "45") (name "Net-(U3-UD+)") (class "Default")
      (node (ref "J20") (pin "A6") (pinfunction "D+_A6") (pintype "bidirectional"))
      (node (ref "J20") (pin "B6") (pinfunction "D+_B6") (pintype "bidirectional"))
      (node (ref "U3") (pin "5") (pinfunction "UD+_5") (pintype "bidirectional"))
    )
    (net (code "46") (name "Net-(U3-UD-)") (class "Default")
      (node (ref "J20") (pin "A7") (pinfunction "D-_A7") (pintype "bidirectional"))
      (node (ref "J20") (pin "B7") (pinfunction "D-_B7") (pintype "bidirectional"))
      (node (ref "U3") (pin "6") (pinfunction "UD-_6") (pintype "bidirectional"))
    )
    (net (code "47") (name "Net-(U3-V3)") (class "Default")
      (node (ref "C17") (pin "1") (pinfunction "1_1") (pintype "passive"))
      (node (ref "U3") (pin "4") (pinfunction "V3_4") (pintype "bidirectional"))
    )
    (net (code "48") (name "PI-5V") (class "Default")
      (node (ref "C4") (pin "1") (pinfunction "1_1") (pintype "passive"))
      (node (ref "C8") (pin "1") (pinfunction "1_1") (pintype "passive"))
      (node (ref "JP4") (pin "1") (pinfunction "1_1") (pintype "passive"))
      (node (ref "Q10") (pin "4") (pinfunction "E_4") (pintype "passive"))
      (node (ref "Q12") (pin "3") (pinfunction "D_3") (pintype "bidirectional"))
      (node (ref "Q7") (pin "2") (pinfunction "S_2") (pintype "bidirectional"))
      (node (ref "Q8") (pin "4") (pinfunction "E_4") (pintype "passive"))
      (node (ref "Q9") (pin "2") (pinfunction "S_2") (pintype "bidirectional"))
      (node (ref "R1") (pin "2") (pinfunction "2_2") (pintype "passive"))
      (node (ref "R18") (pin "2") (pinfunction "2_2") (pintype "passive"))
      (node (ref "R19") (pin "2") (pinfunction "2_2") (pintype "passive"))
      (node (ref "R2") (pin "2") (pinfunction "2_2") (pintype "passive"))
      (node (ref "TP24") (pin "P$1") (pinfunction "1_P$1") (pintype "bidirectional"))
      (node (ref "U1") (pin "28") (pinfunction "VDD_28") (pintype "bidirectional"))
      (node (ref "U2") (pin "5") (pinfunction "P$V+_5") (pintype "bidirectional"))
    )
    (net (code "49") (name "PI-RXI") (class "Default")
      (node (ref "J1") (pin "10") (pinfunction "RXI_10") (pintype "input"))
      (node (ref "S1") (pin "2") (pinfunction "P_2") (pintype "passive"))
      (node (ref "TP26") (pin "P$1") (pinfunction "1_P$1") (pintype "bidirectional"))
    )
    (net (code "50") (name "PI-TXO") (class "Default")
      (node (ref "D2") (pin "C") (pinfunction "C_C") (pintype "passive"))
      (node (ref "J1") (pin "8") (pinfunction "TXO_8") (pintype "output"))
      (node (ref "J21") (pin "1") (pinfunction "1_1") (pintype "passive"))
      (node (ref "TP20") (pin "P$1") (pinfunction "1_P$1") (pintype "bidirectional"))
      (node (ref "U3") (pin "3") (pinfunction "RXI_3") (pintype "bidirectional"))
    )
    (net (code "51") (name "RVR-5V") (class "Default")
      (node (ref "J21") (pin "4") (pinfunction "4_4") (pintype "passive"))
      (node (ref "Q2") (pin "3") (pinfunction "D_3") (pintype "bidirectional"))
      (node (ref "Q3") (pin "1") (pinfunction "E_1") (pintype "passive"))
      (node (ref "Q7") (pin "3") (pinfunction "D_3") (pintype "bidirectional"))
      (node (ref "Q8") (pin "1") (pinfunction "E_1") (pintype "passive"))
      (node (ref "R20") (pin "2") (pinfunction "2_2") (pintype "passive"))
      (node (ref "TP25") (pin "P$1") (pinfunction "1_P$1") (pintype "bidirectional"))
      (node (ref "U2") (pin "1") (pinfunction "A_1") (pintype "bidirectional"))
    )
    (net (code "52") (name "RVR-TXO") (class "Default")
      (node (ref "J21") (pin "2") (pinfunction "2_2") (pintype "passive"))
      (node (ref "S1") (pin "3") (pinfunction "S_3") (pintype "passive"))
      (node (ref "TP21") (pin "P$1") (pinfunction "1_P$1") (pintype "bidirectional"))
    )
    (net (code "53") (name "SERVO") (class "Default")
      (node (ref "C5") (pin "+") (pinfunction "+_+") (pintype "passive"))
      (node (ref "C6") (pin "1") (pinfunction "1_1") (pintype "passive"))
      (node (ref "J10") (pin "2") (pinfunction "2_2") (pintype "passive"))
      (node (ref "J11") (pin "2") (pinfunction "2_2") (pintype "passive"))
      (node (ref "J12") (pin "2") (pinfunction "2_2") (pintype "passive"))
      (node (ref "J13") (pin "2") (pinfunction "2_2") (pintype "passive"))
      (node (ref "J14") (pin "2") (pinfunction "2_2") (pintype "passive"))
      (node (ref "J15") (pin "2") (pinfunction "2_2") (pintype "passive"))
      (node (ref "J16") (pin "2") (pinfunction "2_2") (pintype "passive"))
      (node (ref "J17") (pin "2") (pinfunction "2_2") (pintype "passive"))
      (node (ref "J18") (pin "2") (pinfunction "2_2") (pintype "passive"))
      (node (ref "J3") (pin "2") (pinfunction "2_2") (pintype "passive"))
      (node (ref "J4") (pin "2") (pinfunction "2_2") (pintype "passive"))
      (node (ref "J5") (pin "2") (pinfunction "2_2") (pintype "passive"))
      (node (ref "J6") (pin "2") (pinfunction "2_2") (pintype "passive"))
      (node (ref "J7") (pin "2") (pinfunction "2_2") (pintype "passive"))
      (node (ref "J8") (pin "2") (pinfunction "2_2") (pintype "passive"))
      (node (ref "J9") (pin "2") (pinfunction "2_2") (pintype "passive"))
      (node (ref "Q12") (pin "2") (pinfunction "S_2") (pintype "bidirectional"))
      (node (ref "Q2") (pin "2") (pinfunction "S_2") (pintype "bidirectional"))
      (node (ref "Q3") (pin "4") (pinfunction "E_4") (pintype "passive"))
      (node (ref "Q5") (pin "2") (pinfunction "S_2") (pintype "bidirectional"))
      (node (ref "Q6") (pin "4") (pinfunction "E_4") (pintype "passive"))
      (node (ref "TP16") (pin "P$1") (pinfunction "1_P$1") (pintype "bidirectional"))
    )
    (net (code "54") (name "SHLD") (class "Default")
      (node (ref "J20") (pin "SHLD1") (pinfunction "SHLD_SHLD1") (pintype "bidirectional"))
      (node (ref "J20") (pin "SHLD2") (pinfunction "SHLD_SHLD2") (pintype "bidirectional"))
      (node (ref "J20") (pin "SHLD3") (pinfunction "SHLD_SHLD3") (pintype "bidirectional"))
      (node (ref "J20") (pin "SHLD4") (pinfunction "SHLD_SHLD4") (pintype "bidirectional"))
      (node (ref "J20") (pin "SHLD5") (pinfunction "SHLD_SHLD5") (pintype "bidirectional"))
      (node (ref "J20") (pin "SHLD6") (pinfunction "SHLD_SHLD6") (pintype "bidirectional"))
      (node (ref "J20") (pin "SHLD7") (pinfunction "SHLD_SHLD7") (pintype "bidirectional"))
      (node (ref "J20") (pin "SHLD8") (pinfunction "SHLD_SHLD8") (pintype "bidirectional"))
    )
    (net (code "55") (name "USB-5V") (class "Default")
      (node (ref "F2") (pin "2") (pinfunction "2_2") (pintype "bidirectional"))
      (node (ref "JP2") (pin "2") (pinfunction "2_2") (pintype "passive"))
      (node (ref "Q10") (pin "1") (pinfunction "E_1") (pintype "passive"))
      (node (ref "Q5") (pin "3") (pinfunction "D_3") (pintype "bidirectional"))
      (node (ref "Q6") (pin "1") (pinfunction "E_1") (pintype "passive"))
      (node (ref "Q9") (pin "3") (pinfunction "D_3") (pintype "bidirectional"))
      (node (ref "R21") (pin "2") (pinfunction "2_2") (pintype "passive"))
      (node (ref "U2") (pin "2") (pinfunction "B_2") (pintype "bidirectional"))
    )
    (net (code "56") (name "unconnected-(J1-CE0-Pad24)") (class "Default")
      (node (ref "J1") (pin "24") (pinfunction "CE0_24") (pintype "output"))
    )
    (net (code "57") (name "unconnected-(J1-CE1-Pad26)") (class "Default")
      (node (ref "J1") (pin "26") (pinfunction "CE1_26") (pintype "output"))
    )
    (net (code "58") (name "unconnected-(J1-GP4-Pad7)") (class "Default")
      (node (ref "J1") (pin "7") (pinfunction "GP4_7") (pintype "bidirectional"))
    )
    (net (code "59") (name "unconnected-(J1-GP5-Pad29)") (class "Default")
      (node (ref "J1") (pin "29") (pinfunction "GP5_29") (pintype "bidirectional"))
    )
    (net (code "60") (name "unconnected-(J1-GP6-Pad31)") (class "Default")
      (node (ref "J1") (pin "31") (pinfunction "GP6_31") (pintype "bidirectional"))
    )
    (net (code "61") (name "unconnected-(J1-GP12-Pad32)") (class "Default")
      (node (ref "J1") (pin "32") (pinfunction "GP12_32") (pintype "bidirectional"))
    )
    (net (code "62") (name "unconnected-(J1-GP13-Pad33)") (class "Default")
      (node (ref "J1") (pin "33") (pinfunction "GP13_33") (pintype "bidirectional"))
    )
    (net (code "63") (name "unconnected-(J1-GP16-Pad36)") (class "Default")
      (node (ref "J1") (pin "36") (pinfunction "GP16_36") (pintype "bidirectional"))
    )
    (net (code "64") (name "unconnected-(J1-GP17-Pad11)") (class "Default")
      (node (ref "J1") (pin "11") (pinfunction "GP17_11") (pintype "bidirectional"))
    )
    (net (code "65") (name "unconnected-(J1-GP18#-Pad12)") (class "Default")
      (node (ref "J1") (pin "12") (pinfunction "GP18#_12") (pintype "bidirectional"))
    )
    (net (code "66") (name "unconnected-(J1-GP19-Pad35)") (class "Default")
      (node (ref "J1") (pin "35") (pinfunction "GP19_35") (pintype "bidirectional"))
    )
    (net (code "67") (name "unconnected-(J1-GP20-Pad38)") (class "Default")
      (node (ref "J1") (pin "38") (pinfunction "GP20_38") (pintype "bidirectional"))
    )
    (net (code "68") (name "unconnected-(J1-GP21-Pad40)") (class "Default")
      (node (ref "J1") (pin "40") (pinfunction "GP21_40") (pintype "bidirectional"))
    )
    (net (code "69") (name "unconnected-(J1-GP22-Pad15)") (class "Default")
      (node (ref "J1") (pin "15") (pinfunction "GP22_15") (pintype "bidirectional"))
    )
    (net (code "70") (name "unconnected-(J1-GP23-Pad16)") (class "Default")
      (node (ref "J1") (pin "16") (pinfunction "GP23_16") (pintype "bidirectional"))
    )
    (net (code "71") (name "unconnected-(J1-GP24-Pad18)") (class "Default")
      (node (ref "J1") (pin "18") (pinfunction "GP24_18") (pintype "bidirectional"))
    )
    (net (code "72") (name "unconnected-(J1-GP25-Pad22)") (class "Default")
      (node (ref "J1") (pin "22") (pinfunction "GP25_22") (pintype "bidirectional"))
    )
    (net (code "73") (name "unconnected-(J1-GP26-Pad37)") (class "Default")
      (node (ref "J1") (pin "37") (pinfunction "GP26_37") (pintype "bidirectional"))
    )
    (net (code "74") (name "unconnected-(J1-GP27-Pad13)") (class "Default")
      (node (ref "J1") (pin "13") (pinfunction "GP27_13") (pintype "bidirectional"))
    )
    (net (code "75") (name "unconnected-(J1-ID_SC-Pad28)") (class "Default")
      (node (ref "J1") (pin "28") (pinfunction "ID_SC_28") (pintype "bidirectional"))
    )
    (net (code "76") (name "unconnected-(J1-ID_SD-Pad27)") (class "Default")
      (node (ref "J1") (pin "27") (pinfunction "ID_SD_27") (pintype "bidirectional"))
    )
    (net (code "77") (name "unconnected-(J1-MISO-Pad21)") (class "Default")
      (node (ref "J1") (pin "21") (pinfunction "MISO_21") (pintype "input"))
    )
    (net (code "78") (name "unconnected-(J1-MOSI-Pad19)") (class "Default")
      (node (ref "J1") (pin "19") (pinfunction "MOSI_19") (pintype "output"))
    )
    (net (code "79") (name "unconnected-(J1-SCLK-Pad23)") (class "Default")
      (node (ref "J1") (pin "23") (pinfunction "SCLK_23") (pintype "output"))
    )
    (net (code "80") (name "unconnected-(U1-A0-Pad1)") (class "Default")
      (node (ref "U1") (pin "1") (pinfunction "A0_1") (pintype "bidirectional"))
    )
    (net (code "81") (name "unconnected-(U1-A1-Pad2)") (class "Default")
      (node (ref "U1") (pin "2") (pinfunction "A1_2") (pintype "bidirectional"))
    )
    (net (code "82") (name "unconnected-(U1-A2-Pad3)") (class "Default")
      (node (ref "U1") (pin "3") (pinfunction "A2_3") (pintype "bidirectional"))
    )
    (net (code "83") (name "unconnected-(U1-A3-Pad4)") (class "Default")
      (node (ref "U1") (pin "4") (pinfunction "A3_4") (pintype "bidirectional"))
    )
    (net (code "84") (name "unconnected-(U1-A4-Pad5)") (class "Default")
      (node (ref "U1") (pin "5") (pinfunction "A4_5") (pintype "bidirectional"))
    )
    (net (code "85") (name "unconnected-(U1-A5-Pad24)") (class "Default")
      (node (ref "U1") (pin "24") (pinfunction "A5_24") (pintype "bidirectional"))
    )
    (net (code "86") (name "unconnected-(U3-R232-Pad15)") (class "Default")
      (node (ref "U3") (pin "15") (pinfunction "R232_15") (pintype "bidirectional"))
    )
    (net (code "87") (name "unconnected-(U3-~{CTS}-Pad9)") (class "Default")
      (node (ref "U3") (pin "9") (pinfunction "~{CTS}_9") (pintype "bidirectional"))
    )
    (net (code "88") (name "unconnected-(U3-~{DCD}-Pad12)") (class "Default")
      (node (ref "U3") (pin "12") (pinfunction "~{DCD}_12") (pintype "bidirectional"))
    )
    (net (code "89") (name "unconnected-(U3-~{DSR}-Pad10)") (class "Default")
      (node (ref "U3") (pin "10") (pinfunction "~{DSR}_10") (pintype "bidirectional"))
    )
    (net (code "90") (name "unconnected-(U3-~{DTR}-Pad13)") (class "Default")
      (node (ref "U3") (pin "13") (pinfunction "~{DTR}_13") (pintype "bidirectional"))
    )
    (net (code "91") (name "unconnected-(U3-~{RI}-Pad11)") (class "Default")
      (node (ref "U3") (pin "11") (pinfunction "~{RI}_11") (pintype "bidirectional"))
    )
    (net (code "92") (name "unconnected-(U3-~{RTS}-Pad14)") (class "Default")
      (node (ref "U3") (pin "14") (pinfunction "~{RTS}_14") (pintype "bidirectional"))
    )
  )
)
